# offzone-addon-s7-easyeda-sheet.net
KiCad netlist of a schematic drawn in EasyEDA
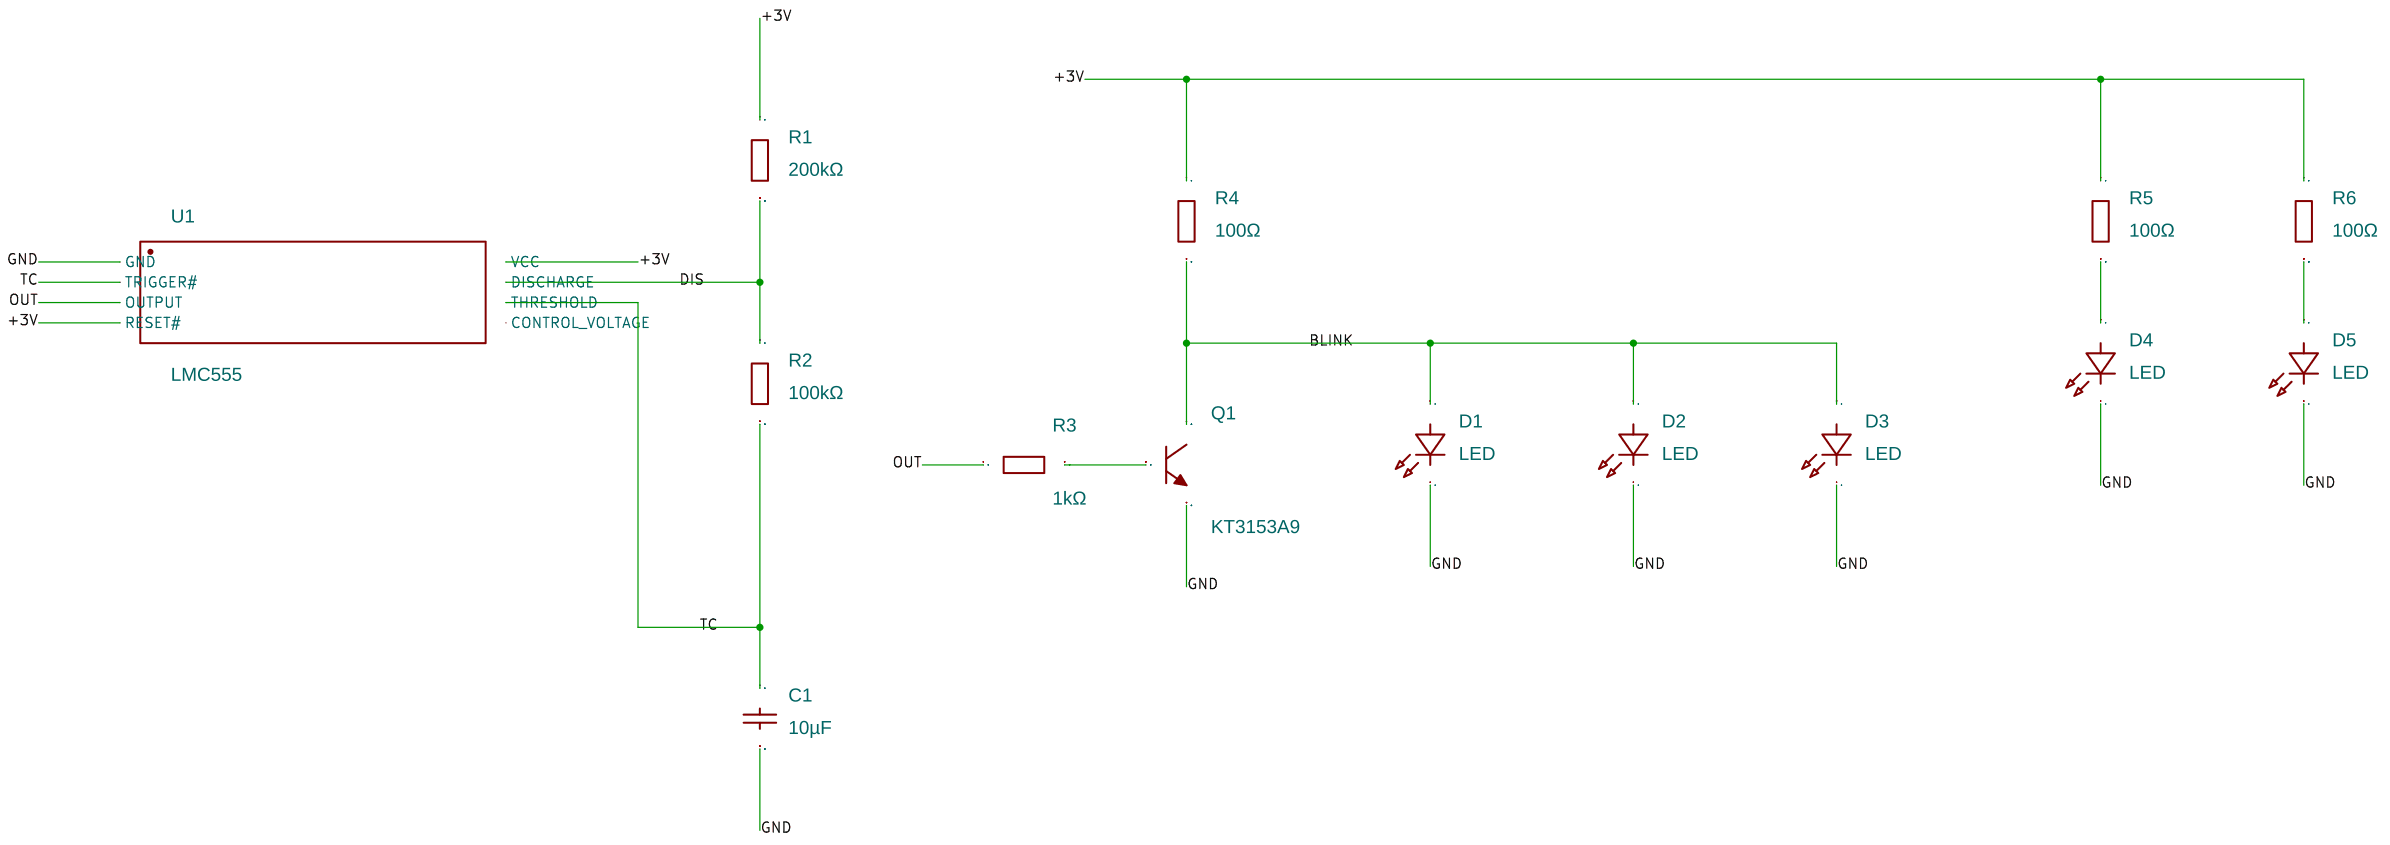
[diagram p0: schematic sheet]

(export (version "E")
  (design (tool "Eeschema 10.0.6"))
  (components
    (comp (ref "C1")
      (value "10µF")
      (fields
        (field (name "BOM_Manufacturer Part") "CL21A106KOQNNNE")
        (field (name "BOM_Supplier Part") "C1713")
      )
      (libsource (lib "") (part "CL21A106KOQNNNE"))
    )
    (comp (ref "D1")
      (value "LED")
      (fields
        (field (name "BOM_Manufacturer Part") "17-21/R6C-AQ2R2B/4T")
        (field (name "BOM_Supplier Part") "C2971979")
      )
      (libsource (lib "") (part "17-21/R6C-AQ2R2B/4T"))
    )
    (comp (ref "D2")
      (value "LED")
      (fields
        (field (name "BOM_Manufacturer Part") "17-21/R6C-AQ2R2B/4T")
        (field (name "BOM_Supplier Part") "C2971979")
      )
      (libsource (lib "") (part "17-21/R6C-AQ2R2B/4T"))
    )
    (comp (ref "D3")
      (value "LED")
      (fields
        (field (name "BOM_Manufacturer Part") "17-21/R6C-AQ2R2B/4T")
        (field (name "BOM_Supplier Part") "C2971979")
      )
      (libsource (lib "") (part "17-21/R6C-AQ2R2B/4T"))
    )
    (comp (ref "D4")
      (value "LED")
      (fields
        (field (name "BOM_Manufacturer Part") "17-21/R6C-AQ2R2B/4T")
        (field (name "BOM_Supplier Part") "C2971979")
      )
      (libsource (lib "") (part "17-21/R6C-AQ2R2B/4T"))
    )
    (comp (ref "D5")
      (value "LED")
      (fields
        (field (name "BOM_Manufacturer Part") "17-21/R6C-AQ2R2B/4T")
        (field (name "BOM_Supplier Part") "C2971979")
      )
      (libsource (lib "") (part "17-21/R6C-AQ2R2B/4T"))
    )
    (comp (ref "Q1")
      (value "KT3153A9")
      (fields (field (name "BOM_Manufacturer Part") "КТ3153А9"))
      (libsource (lib "") (part "KT3153A9"))
    )
    (comp (ref "R1")
      (value "200kΩ")
      (fields
        (field (name "BOM_Manufacturer Part") "0603WAF2003T5E")
        (field (name "BOM_Supplier Part") "C25811")
      )
      (libsource (lib "") (part "0603WAF2003T5E"))
    )
    (comp (ref "R2")
      (value "100kΩ")
      (fields
        (field (name "BOM_Manufacturer Part") "0603WAF1003T5E")
        (field (name "BOM_Supplier Part") "C25803")
      )
      (libsource (lib "") (part "0603WAF1003T5E"))
    )
    (comp (ref "R3")
      (value "1kΩ")
      (fields
        (field (name "BOM_Manufacturer Part") "0603WAF1001T5E")
        (field (name "BOM_Supplier Part") "C21190")
      )
      (libsource (lib "") (part "0603WAF1001T5E"))
    )
    (comp (ref "R4")
      (value "100Ω")
      (fields
        (field (name "BOM_Manufacturer Part") "RC0603FR-07100RL")
        (field (name "BOM_Supplier Part") "C105588")
      )
      (libsource (lib "") (part "RC0603FR-07100RL"))
    )
    (comp (ref "R5")
      (value "100Ω")
      (fields
        (field (name "BOM_Manufacturer Part") "RC0603FR-07100RL")
        (field (name "BOM_Supplier Part") "C105588")
      )
      (libsource (lib "") (part "RC0603FR-07100RL"))
    )
    (comp (ref "R6")
      (value "100Ω")
      (fields
        (field (name "BOM_Manufacturer Part") "RC0603FR-07100RL")
        (field (name "BOM_Supplier Part") "C105588")
      )
      (libsource (lib "") (part "RC0603FR-07100RL"))
    )
    (comp (ref "U1")
      (value "LMC555")
      (fields
        (field (name "BOM_Manufacturer Part") "LMC555M/TR")
        (field (name "BOM_Supplier Part") "C356725")
      )
      (libsource (lib "") (part "LMC555M/TR"))
    )
  )
  (nets
    (net (code "1") (name "/+3V") (class "Default")
      (node (ref "R1") (pin "1") (pinfunction "1_1") (pintype "input"))
      (node (ref "R4") (pin "1") (pinfunction "1_1") (pintype "input"))
      (node (ref "R5") (pin "1") (pinfunction "1_1") (pintype "input"))
      (node (ref "R6") (pin "1") (pinfunction "1_1") (pintype "input"))
      (node (ref "U1") (pin "4") (pinfunction "RESET#_4") (pintype "unspecified"))
      (node (ref "U1") (pin "8") (pinfunction "VCC_8") (pintype "unspecified"))
    )
    (net (code "2") (name "/BLINK") (class "Default")
      (node (ref "D1") (pin "2") (pinfunction "A_2") (pintype "unspecified"))
      (node (ref "D2") (pin "2") (pinfunction "A_2") (pintype "unspecified"))
      (node (ref "D3") (pin "2") (pinfunction "A_2") (pintype "unspecified"))
      (node (ref "Q1") (pin "1") (pinfunction "3_1") (pintype "input"))
      (node (ref "R4") (pin "2") (pinfunction "2_2") (pintype "input"))
    )
    (net (code "3") (name "/DIS") (class "Default")
      (node (ref "R1") (pin "2") (pinfunction "2_2") (pintype "input"))
      (node (ref "R2") (pin "1") (pinfunction "1_1") (pintype "input"))
      (node (ref "U1") (pin "7") (pinfunction "DISCHARGE_7") (pintype "unspecified"))
    )
    (net (code "4") (name "/GND") (class "Default")
      (node (ref "C1") (pin "2") (pinfunction "2_2") (pintype "input"))
      (node (ref "D1") (pin "1") (pinfunction "K_1") (pintype "unspecified"))
      (node (ref "D2") (pin "1") (pinfunction "K_1") (pintype "unspecified"))
      (node (ref "D3") (pin "1") (pinfunction "K_1") (pintype "unspecified"))
      (node (ref "D4") (pin "1") (pinfunction "K_1") (pintype "unspecified"))
      (node (ref "D5") (pin "1") (pinfunction "K_1") (pintype "unspecified"))
      (node (ref "Q1") (pin "3") (pinfunction "2_3") (pintype "input"))
      (node (ref "U1") (pin "1") (pinfunction "GND_1") (pintype "unspecified"))
    )
    (net (code "5") (name "/OUT") (class "Default")
      (node (ref "R3") (pin "1") (pinfunction "1_1") (pintype "input"))
      (node (ref "U1") (pin "3") (pinfunction "OUTPUT_3") (pintype "unspecified"))
    )
    (net (code "6") (name "/TC") (class "Default")
      (node (ref "C1") (pin "1") (pinfunction "1_1") (pintype "input"))
      (node (ref "R2") (pin "2") (pinfunction "2_2") (pintype "input"))
      (node (ref "U1") (pin "2") (pinfunction "TRIGGER#_2") (pintype "unspecified"))
      (node (ref "U1") (pin "6") (pinfunction "THRESHOLD_6") (pintype "unspecified"))
    )
    (net (code "7") (name "Net-(D4-A)") (class "Default")
      (node (ref "D4") (pin "2") (pinfunction "A_2") (pintype "unspecified"))
      (node (ref "R5") (pin "2") (pinfunction "2_2") (pintype "input"))
    )
    (net (code "8") (name "Net-(D5-A)") (class "Default")
      (node (ref "D5") (pin "2") (pinfunction "A_2") (pintype "unspecified"))
      (node (ref "R6") (pin "2") (pinfunction "2_2") (pintype "input"))
    )
    (net (code "9") (name "Net-(Q1-1)") (class "Default")
      (node (ref "Q1") (pin "2") (pinfunction "1_2") (pintype "input"))
      (node (ref "R3") (pin "2") (pinfunction "2_2") (pintype "input"))
    )
    (net (code "10") (name "unconnected-(U1-CONTROL_VOLTAGE-Pad5)") (class "Default")
      (node (ref "U1") (pin "5") (pinfunction "CONTROL_VOLTAGE_5") (pintype "unspecified"))
    )
  )
)
